# ATTINY-warmthV0_5.net
KiCad netlist of a schematic drawn in EAGLE
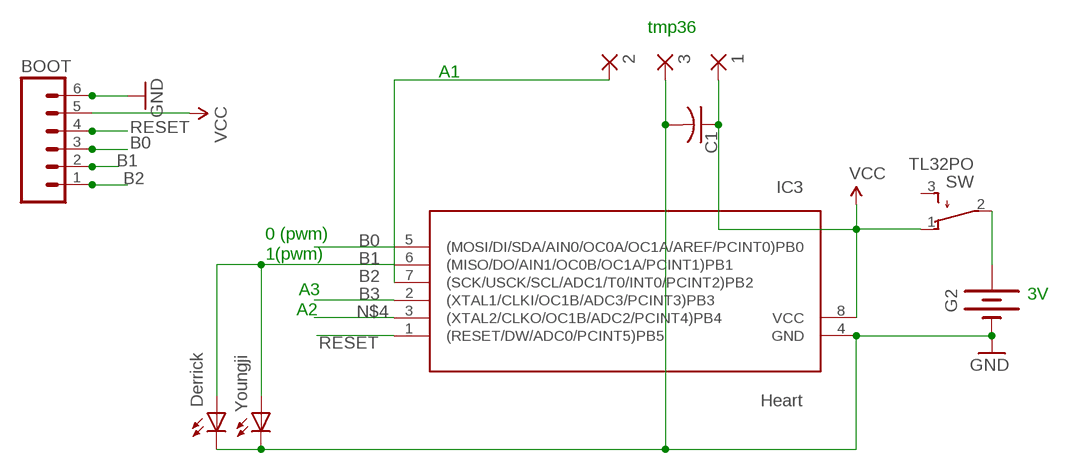
[diagram p0: schematic, sheet 1]

(export (version "E")
  (design (tool "Eeschema 10.0.6"))
  (components
    (comp (ref "1")
      (value "WIREPADSMD1,27-254")
      (footprint "eagle-import:SMD1,27-2,54")
      (libsource (lib "eagle-import") (part "WIREPADSMD1,27-254"))
    )
    (comp (ref "2")
      (value "WIREPADSMD1,27-254")
      (footprint "eagle-import:SMD1,27-2,54")
      (libsource (lib "eagle-import") (part "WIREPADSMD1,27-254"))
    )
    (comp (ref "3")
      (value "WIREPADSMD1,27-254")
      (footprint "eagle-import:SMD1,27-2,54")
      (libsource (lib "eagle-import") (part "WIREPADSMD1,27-254"))
    )
    (comp (ref "BOOT")
      (value "M06SIP")
      (footprint "eagle-import:1X06")
      (libsource (lib "eagle-import") (part "M06SIP"))
    )
    (comp (ref "C1")
      (value "C-USC0805K")
      (footprint "eagle-import:C0805K")
      (libsource (lib "eagle-import") (part "C-USC0805K"))
    )
    (comp (ref "G2")
      (value "BATTERY20SMD")
      (footprint "eagle-import:BATTCON_20MM")
      (libsource (lib "eagle-import") (part "BATTERY20SMD"))
    )
    (comp (ref "IC3")
      (value "Heart")
      (footprint "eagle-import:SOIC8")
      (libsource (lib "eagle-import") (part "ATTINY85SV-10"))
    )
    (comp (ref "SW")
      (value "TL32PO")
      (footprint "eagle-import:TL3XPO")
      (libsource (lib "eagle-import") (part "TL32PO"))
    )
    (comp (ref "TX")
      (value "Derrick")
      (footprint "eagle-import:LED3MM")
      (libsource (lib "eagle-import") (part "LED3MM"))
    )
    (comp (ref "TX1")
      (value "Youngji")
      (footprint "eagle-import:LED3MM")
      (libsource (lib "eagle-import") (part "LED3MM"))
    )
  )
  (nets
    (net (code "1") (name "/B0") (class "Default")
      (node (ref "BOOT") (pin "3") (pinfunction "3_3") (pintype "passive"))
      (node (ref "IC3") (pin "5") (pinfunction "(MOSI/DI/SDA/AIN0/OC0A/OC1A/AREF/PCINT0)PB0_5") (pintype "bidirectional"))
    )
    (net (code "2") (name "/B1") (class "Default")
      (node (ref "BOOT") (pin "2") (pinfunction "2_2") (pintype "passive"))
      (node (ref "IC3") (pin "6") (pinfunction "(MISO/DO/AIN1/OC0B/OC1A/PCINT1)PB1_6") (pintype "bidirectional"))
      (node (ref "TX") (pin "A") (pinfunction "A_A") (pintype "passive"))
      (node (ref "TX1") (pin "A") (pinfunction "A_A") (pintype "passive"))
    )
    (net (code "3") (name "/B2") (class "Default")
      (node (ref "2") (pin "1") (pinfunction "P_1") (pintype "passive"))
      (node (ref "BOOT") (pin "1") (pinfunction "1_1") (pintype "passive"))
      (node (ref "IC3") (pin "7") (pinfunction "(SCK/USCK/SCL/ADC1/T0/INT0/PCINT2)PB2_7") (pintype "bidirectional"))
    )
    (net (code "4") (name "/B3") (class "Default")
      (node (ref "IC3") (pin "2") (pinfunction "(XTAL1/CLKI/OC1B/ADC3/PCINT3)PB3_2") (pintype "bidirectional"))
    )
    (net (code "5") (name "/N$4") (class "Default")
      (node (ref "IC3") (pin "3") (pinfunction "(XTAL2/CLKO/OC1B/ADC2/PCINT4)PB4_3") (pintype "bidirectional"))
    )
    (net (code "6") (name "/RESET") (class "Default")
      (node (ref "BOOT") (pin "4") (pinfunction "4_4") (pintype "passive"))
      (node (ref "IC3") (pin "1") (pinfunction "(RESET/DW/ADC0/PCINT5)PB5_1") (pintype "bidirectional"))
    )
    (net (code "7") (name "GND") (class "Default")
      (node (ref "3") (pin "1") (pinfunction "P_1") (pintype "passive"))
      (node (ref "BOOT") (pin "6") (pinfunction "6_6") (pintype "passive"))
      (node (ref "C1") (pin "2") (pinfunction "2_2") (pintype "passive"))
      (node (ref "G2") (pin "2") (pinfunction "-_2") (pintype "power_in"))
      (node (ref "IC3") (pin "4") (pinfunction "GND_4") (pintype "bidirectional"))
      (node (ref "TX") (pin "K") (pinfunction "C_K") (pintype "passive"))
      (node (ref "TX1") (pin "K") (pinfunction "C_K") (pintype "passive"))
    )
    (net (code "8") (name "Net-(G2-+)") (class "Default")
      (node (ref "G2") (pin "1") (pinfunction "+_1") (pintype "power_in"))
      (node (ref "SW") (pin "2") (pinfunction "P_2") (pintype "passive"))
    )
    (net (code "9") (name "VCC") (class "Default")
      (node (ref "1") (pin "1") (pinfunction "P_1") (pintype "passive"))
      (node (ref "BOOT") (pin "5") (pinfunction "5_5") (pintype "passive"))
      (node (ref "C1") (pin "1") (pinfunction "1_1") (pintype "passive"))
      (node (ref "IC3") (pin "8") (pinfunction "VCC_8") (pintype "bidirectional"))
      (node (ref "SW") (pin "1") (pinfunction "O_1") (pintype "passive"))
    )
    (net (code "10") (name "unconnected-(SW-S-Pad3)") (class "Default")
      (node (ref "SW") (pin "3") (pinfunction "S_3") (pintype "passive"))
    )
  )
)
